# placappal.net
KiCad netlist of a schematic drawn in EAGLE
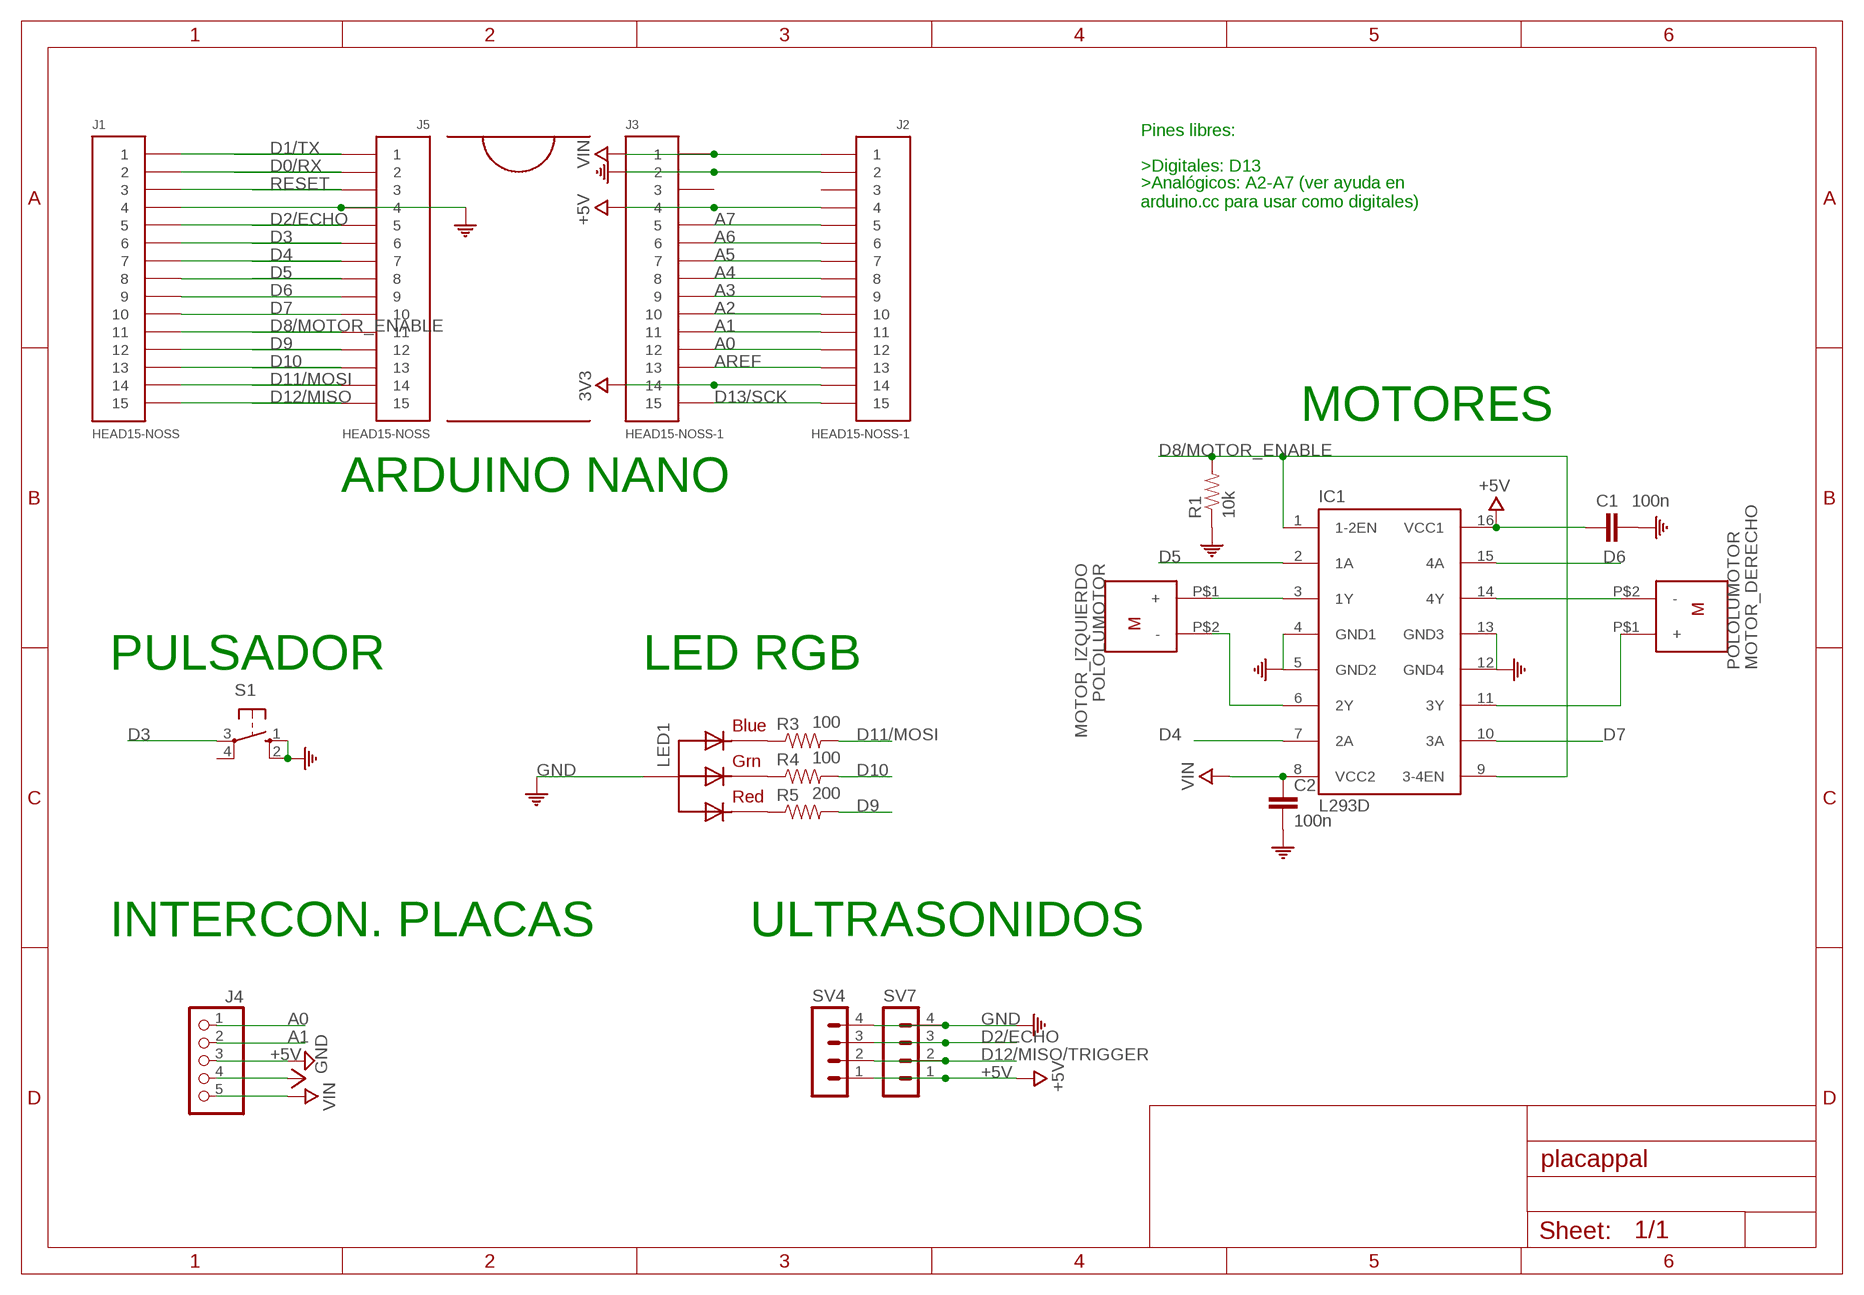
[diagram p0: schematic, sheet 1]

(export (version "E")
  (design (tool "Eeschema 10.0.6"))
  (components
    (comp (ref "C1")
      (value "100n")
      (footprint "eagle-import:1206")
      (libsource (lib "eagle-import") (part "CAP1206"))
    )
    (comp (ref "C2")
      (value "100n")
      (footprint "eagle-import:1206")
      (libsource (lib "eagle-import") (part "CAP1206"))
    )
    (comp (ref "IC1")
      (value "L293D")
      (footprint "eagle-import:DIL16")
      (libsource (lib "eagle-import") (part "L293D"))
    )
    (comp (ref "J1")
      (value "HEAD15-NOSS")
      (footprint "eagle-import:HEAD15-NOSS")
      (libsource (lib "eagle-import") (part "HEAD15-NOSS"))
    )
    (comp (ref "J2")
      (value "HEAD15-NOSS-1")
      (footprint "eagle-import:HEAD15-NOSS-1")
      (libsource (lib "eagle-import") (part "HEAD15-NOSS-1"))
    )
    (comp (ref "J3")
      (value "HEAD15-NOSS-1")
      (footprint "eagle-import:HEAD15-NOSS-1")
      (libsource (lib "eagle-import") (part "HEAD15-NOSS-1"))
    )
    (comp (ref "J4")
      (value "PINHD-1X5")
      (footprint "eagle-import:1X05")
      (libsource (lib "eagle-import") (part "PINHD-1X5"))
    )
    (comp (ref "J5")
      (value "HEAD15-NOSS")
      (footprint "eagle-import:HEAD15-NOSS")
      (libsource (lib "eagle-import") (part "HEAD15-NOSS"))
    )
    (comp (ref "LED1")
      (value "RGBLED_CA-5MM")
      (footprint "eagle-import:LED5MMRGB")
      (libsource (lib "eagle-import") (part "RGBLED_CA-5MM"))
    )
    (comp (ref "MOTOR_DERECHO")
      (value "POLOLUMOTOR")
      (footprint "eagle-import:N20MOTOR")
      (libsource (lib "eagle-import") (part "POLOLUMOTOR"))
    )
    (comp (ref "MOTOR_IZQUIERDO")
      (value "POLOLUMOTOR")
      (footprint "eagle-import:N20MOTOR")
      (libsource (lib "eagle-import") (part "POLOLUMOTOR"))
    )
    (comp (ref "R1")
      (value "10k")
      (footprint "eagle-import:1206")
      (libsource (lib "eagle-import") (part "RESISTOR1206"))
    )
    (comp (ref "R3")
      (value "100")
      (footprint "eagle-import:1206")
      (libsource (lib "eagle-import") (part "RESISTOR1206"))
    )
    (comp (ref "R4")
      (value "100")
      (footprint "eagle-import:1206")
      (libsource (lib "eagle-import") (part "RESISTOR1206"))
    )
    (comp (ref "R5")
      (value "200")
      (footprint "eagle-import:1206")
      (libsource (lib "eagle-import") (part "RESISTOR1206"))
    )
    (comp (ref "S1")
      (value "10-XX")
      (footprint "eagle-import:B3F-10XX")
      (libsource (lib "eagle-import") (part "10-XX"))
    )
    (comp (ref "SV4")
      (value "MA04-1")
      (footprint "eagle-import:MA04-1")
      (fields (field (name "OC_FARNELL") "unknown") (field (name "OC_NEWARK") "unknown"))
      (libsource (lib "eagle-import") (part "MA04-1"))
    )
    (comp (ref "SV7")
      (value "MA04-1")
      (footprint "eagle-import:MA04-1")
      (fields (field (name "OC_FARNELL") "unknown") (field (name "OC_NEWARK") "unknown"))
      (libsource (lib "eagle-import") (part "MA04-1"))
    )
  )
  (nets
    (net (code "1") (name "+5V") (class "Default")
      (node (ref "C1") (pin "2") (pinfunction "2_2") (pintype "passive"))
      (node (ref "IC1") (pin "16") (pinfunction "VCC1_16") (pintype "power_in"))
      (node (ref "J2") (pin "4") (pinfunction "4_4") (pintype "passive"))
      (node (ref "J3") (pin "4") (pinfunction "4_4") (pintype "passive"))
      (node (ref "J4") (pin "4") (pinfunction "4_4") (pintype "passive"))
      (node (ref "SV4") (pin "1") (pinfunction "1_1") (pintype "passive"))
      (node (ref "SV7") (pin "1") (pinfunction "1_1") (pintype "passive"))
    )
    (net (code "2") (name "/A0") (class "Default")
      (node (ref "J2") (pin "12") (pinfunction "12_12") (pintype "passive"))
      (node (ref "J3") (pin "12") (pinfunction "12_12") (pintype "passive"))
      (node (ref "J4") (pin "1") (pinfunction "1_1") (pintype "passive"))
    )
    (net (code "3") (name "/A1") (class "Default")
      (node (ref "J2") (pin "11") (pinfunction "11_11") (pintype "passive"))
      (node (ref "J3") (pin "11") (pinfunction "11_11") (pintype "passive"))
      (node (ref "J4") (pin "2") (pinfunction "2_2") (pintype "passive"))
    )
    (net (code "4") (name "/A2") (class "Default")
      (node (ref "J2") (pin "10") (pinfunction "10_10") (pintype "passive"))
      (node (ref "J3") (pin "10") (pinfunction "10_10") (pintype "passive"))
    )
    (net (code "5") (name "/A3") (class "Default")
      (node (ref "J2") (pin "9") (pinfunction "9_9") (pintype "passive"))
      (node (ref "J3") (pin "9") (pinfunction "9_9") (pintype "passive"))
    )
    (net (code "6") (name "/A4") (class "Default")
      (node (ref "J2") (pin "8") (pinfunction "8_8") (pintype "passive"))
      (node (ref "J3") (pin "8") (pinfunction "8_8") (pintype "passive"))
    )
    (net (code "7") (name "/A5") (class "Default")
      (node (ref "J2") (pin "7") (pinfunction "7_7") (pintype "passive"))
      (node (ref "J3") (pin "7") (pinfunction "7_7") (pintype "passive"))
    )
    (net (code "8") (name "/A6") (class "Default")
      (node (ref "J2") (pin "6") (pinfunction "6_6") (pintype "passive"))
      (node (ref "J3") (pin "6") (pinfunction "6_6") (pintype "passive"))
    )
    (net (code "9") (name "/A7") (class "Default")
      (node (ref "J2") (pin "5") (pinfunction "5_5") (pintype "passive"))
      (node (ref "J3") (pin "5") (pinfunction "5_5") (pintype "passive"))
    )
    (net (code "10") (name "/AREF") (class "Default")
      (node (ref "J2") (pin "13") (pinfunction "13_13") (pintype "passive"))
      (node (ref "J3") (pin "13") (pinfunction "13_13") (pintype "passive"))
    )
    (net (code "11") (name "/D0{slash}RX") (class "Default")
      (node (ref "J1") (pin "2") (pinfunction "2_2") (pintype "passive"))
      (node (ref "J5") (pin "2") (pinfunction "2_2") (pintype "passive"))
    )
    (net (code "12") (name "/D1{slash}TX") (class "Default")
      (node (ref "J1") (pin "1") (pinfunction "1_1") (pintype "passive"))
      (node (ref "J5") (pin "1") (pinfunction "1_1") (pintype "passive"))
    )
    (net (code "13") (name "/D2{slash}ECHO") (class "Default")
      (node (ref "J1") (pin "5") (pinfunction "5_5") (pintype "passive"))
      (node (ref "J5") (pin "5") (pinfunction "5_5") (pintype "passive"))
      (node (ref "SV4") (pin "3") (pinfunction "3_3") (pintype "passive"))
      (node (ref "SV7") (pin "3") (pinfunction "3_3") (pintype "passive"))
    )
    (net (code "14") (name "/D3") (class "Default")
      (node (ref "J1") (pin "6") (pinfunction "6_6") (pintype "passive"))
      (node (ref "J5") (pin "6") (pinfunction "6_6") (pintype "passive"))
      (node (ref "S1") (pin "3") (pinfunction "P_3") (pintype "passive"))
    )
    (net (code "15") (name "/D4") (class "Default")
      (node (ref "IC1") (pin "7") (pinfunction "2A_7") (pintype "input"))
      (node (ref "J1") (pin "7") (pinfunction "7_7") (pintype "passive"))
      (node (ref "J5") (pin "7") (pinfunction "7_7") (pintype "passive"))
    )
    (net (code "16") (name "/D5") (class "Default")
      (node (ref "IC1") (pin "2") (pinfunction "1A_2") (pintype "input"))
      (node (ref "J1") (pin "8") (pinfunction "8_8") (pintype "passive"))
      (node (ref "J5") (pin "8") (pinfunction "8_8") (pintype "passive"))
    )
    (net (code "17") (name "/D6") (class "Default")
      (node (ref "IC1") (pin "15") (pinfunction "4A_15") (pintype "input"))
      (node (ref "J1") (pin "9") (pinfunction "9_9") (pintype "passive"))
      (node (ref "J5") (pin "9") (pinfunction "9_9") (pintype "passive"))
    )
    (net (code "18") (name "/D7") (class "Default")
      (node (ref "IC1") (pin "10") (pinfunction "3A_10") (pintype "input"))
      (node (ref "J1") (pin "10") (pinfunction "10_10") (pintype "passive"))
      (node (ref "J5") (pin "10") (pinfunction "10_10") (pintype "passive"))
    )
    (net (code "19") (name "/D8{slash}MOTOR_ENABLE") (class "Default")
      (node (ref "IC1") (pin "1") (pinfunction "1-2EN_1") (pintype "input"))
      (node (ref "IC1") (pin "9") (pinfunction "3-4EN_9") (pintype "input"))
      (node (ref "J1") (pin "11") (pinfunction "11_11") (pintype "passive"))
      (node (ref "J5") (pin "11") (pinfunction "11_11") (pintype "passive"))
      (node (ref "R1") (pin "2") (pinfunction "2_2") (pintype "passive"))
    )
    (net (code "20") (name "/D9") (class "Default")
      (node (ref "J1") (pin "12") (pinfunction "12_12") (pintype "passive"))
      (node (ref "J5") (pin "12") (pinfunction "12_12") (pintype "passive"))
      (node (ref "R5") (pin "2") (pinfunction "2_2") (pintype "passive"))
    )
    (net (code "21") (name "/D10") (class "Default")
      (node (ref "J1") (pin "13") (pinfunction "13_13") (pintype "passive"))
      (node (ref "J5") (pin "13") (pinfunction "13_13") (pintype "passive"))
      (node (ref "R4") (pin "2") (pinfunction "2_2") (pintype "passive"))
    )
    (net (code "22") (name "/D11{slash}MOSI") (class "Default")
      (node (ref "J1") (pin "14") (pinfunction "14_14") (pintype "passive"))
      (node (ref "J5") (pin "14") (pinfunction "14_14") (pintype "passive"))
      (node (ref "R3") (pin "2") (pinfunction "2_2") (pintype "passive"))
    )
    (net (code "23") (name "/D12{slash}MISO") (class "Default")
      (node (ref "J1") (pin "15") (pinfunction "15_15") (pintype "passive"))
      (node (ref "J5") (pin "15") (pinfunction "15_15") (pintype "passive"))
    )
    (net (code "24") (name "/D12{slash}MISO{slash}TRIGGER") (class "Default")
      (node (ref "SV4") (pin "2") (pinfunction "2_2") (pintype "passive"))
      (node (ref "SV7") (pin "2") (pinfunction "2_2") (pintype "passive"))
    )
    (net (code "25") (name "/D13{slash}SCK") (class "Default")
      (node (ref "J2") (pin "15") (pinfunction "15_15") (pintype "passive"))
      (node (ref "J3") (pin "15") (pinfunction "15_15") (pintype "passive"))
    )
    (net (code "26") (name "/RESET") (class "Default")
      (node (ref "J1") (pin "3") (pinfunction "3_3") (pintype "passive"))
      (node (ref "J5") (pin "3") (pinfunction "3_3") (pintype "passive"))
    )
    (net (code "27") (name "3V3") (class "Default")
      (node (ref "J2") (pin "14") (pinfunction "14_14") (pintype "passive"))
      (node (ref "J3") (pin "14") (pinfunction "14_14") (pintype "passive"))
    )
    (net (code "28") (name "COM") (class "Default")
      (node (ref "C1") (pin "1") (pinfunction "1_1") (pintype "passive"))
      (node (ref "C2") (pin "2") (pinfunction "2_2") (pintype "passive"))
      (node (ref "IC1") (pin "12") (pinfunction "GND4_12") (pintype "power_in"))
      (node (ref "IC1") (pin "13") (pinfunction "GND3_13") (pintype "power_in"))
      (node (ref "IC1") (pin "4") (pinfunction "GND1_4") (pintype "power_in"))
      (node (ref "IC1") (pin "5") (pinfunction "GND2_5") (pintype "power_in"))
      (node (ref "J1") (pin "4") (pinfunction "4_4") (pintype "passive"))
      (node (ref "J2") (pin "2") (pinfunction "2_2") (pintype "passive"))
      (node (ref "J3") (pin "2") (pinfunction "2_2") (pintype "passive"))
      (node (ref "J4") (pin "3") (pinfunction "3_3") (pintype "passive"))
      (node (ref "J5") (pin "4") (pinfunction "4_4") (pintype "passive"))
      (node (ref "LED1") (pin "2") (pinfunction "VCC_2") (pintype "bidirectional"))
      (node (ref "R1") (pin "1") (pinfunction "1_1") (pintype "passive"))
      (node (ref "S1") (pin "1") (pinfunction "S_1") (pintype "passive"))
      (node (ref "S1") (pin "2") (pinfunction "S1_2") (pintype "passive"))
      (node (ref "SV4") (pin "4") (pinfunction "4_4") (pintype "passive"))
      (node (ref "SV7") (pin "4") (pinfunction "4_4") (pintype "passive"))
    )
    (net (code "29") (name "Net-(IC1-1Y)") (class "Default")
      (node (ref "IC1") (pin "3") (pinfunction "1Y_3") (pintype "output"))
      (node (ref "MOTOR_IZQUIERDO") (pin "P$1") (pinfunction "+_P$1") (pintype "bidirectional"))
    )
    (net (code "30") (name "Net-(IC1-2Y)") (class "Default")
      (node (ref "IC1") (pin "6") (pinfunction "2Y_6") (pintype "output"))
      (node (ref "MOTOR_IZQUIERDO") (pin "P$2") (pinfunction "-_P$2") (pintype "bidirectional"))
    )
    (net (code "31") (name "Net-(IC1-3Y)") (class "Default")
      (node (ref "IC1") (pin "11") (pinfunction "3Y_11") (pintype "output"))
      (node (ref "MOTOR_DERECHO") (pin "P$1") (pinfunction "+_P$1") (pintype "bidirectional"))
    )
    (net (code "32") (name "Net-(IC1-4Y)") (class "Default")
      (node (ref "IC1") (pin "14") (pinfunction "4Y_14") (pintype "output"))
      (node (ref "MOTOR_DERECHO") (pin "P$2") (pinfunction "-_P$2") (pintype "bidirectional"))
    )
    (net (code "33") (name "Net-(LED1-BLUE)") (class "Default")
      (node (ref "LED1") (pin "4") (pinfunction "BLUE_4") (pintype "bidirectional"))
      (node (ref "R3") (pin "1") (pinfunction "1_1") (pintype "passive"))
    )
    (net (code "34") (name "Net-(LED1-GREEN)") (class "Default")
      (node (ref "LED1") (pin "3") (pinfunction "GREEN_3") (pintype "bidirectional"))
      (node (ref "R4") (pin "1") (pinfunction "1_1") (pintype "passive"))
    )
    (net (code "35") (name "Net-(LED1-RED)") (class "Default")
      (node (ref "LED1") (pin "1") (pinfunction "RED_1") (pintype "bidirectional"))
      (node (ref "R5") (pin "1") (pinfunction "1_1") (pintype "passive"))
    )
    (net (code "36") (name "VIN") (class "Default")
      (node (ref "C2") (pin "1") (pinfunction "1_1") (pintype "passive"))
      (node (ref "IC1") (pin "8") (pinfunction "VCC2_8") (pintype "power_in"))
      (node (ref "J2") (pin "1") (pinfunction "1_1") (pintype "passive"))
      (node (ref "J3") (pin "1") (pinfunction "1_1") (pintype "passive"))
      (node (ref "J4") (pin "5") (pinfunction "5_5") (pintype "passive"))
    )
    (net (code "37") (name "unconnected-(J2-Pad3)") (class "Default")
      (node (ref "J2") (pin "3") (pinfunction "3_3") (pintype "passive"))
    )
    (net (code "38") (name "unconnected-(J3-Pad3)") (class "Default")
      (node (ref "J3") (pin "3") (pinfunction "3_3") (pintype "passive"))
    )
    (net (code "39") (name "unconnected-(S1-P1-Pad4)") (class "Default")
      (node (ref "S1") (pin "4") (pinfunction "P1_4") (pintype "passive"))
    )
  )
)
